# Peripherals.net
KiCad netlist of a schematic drawn in Altium Designer
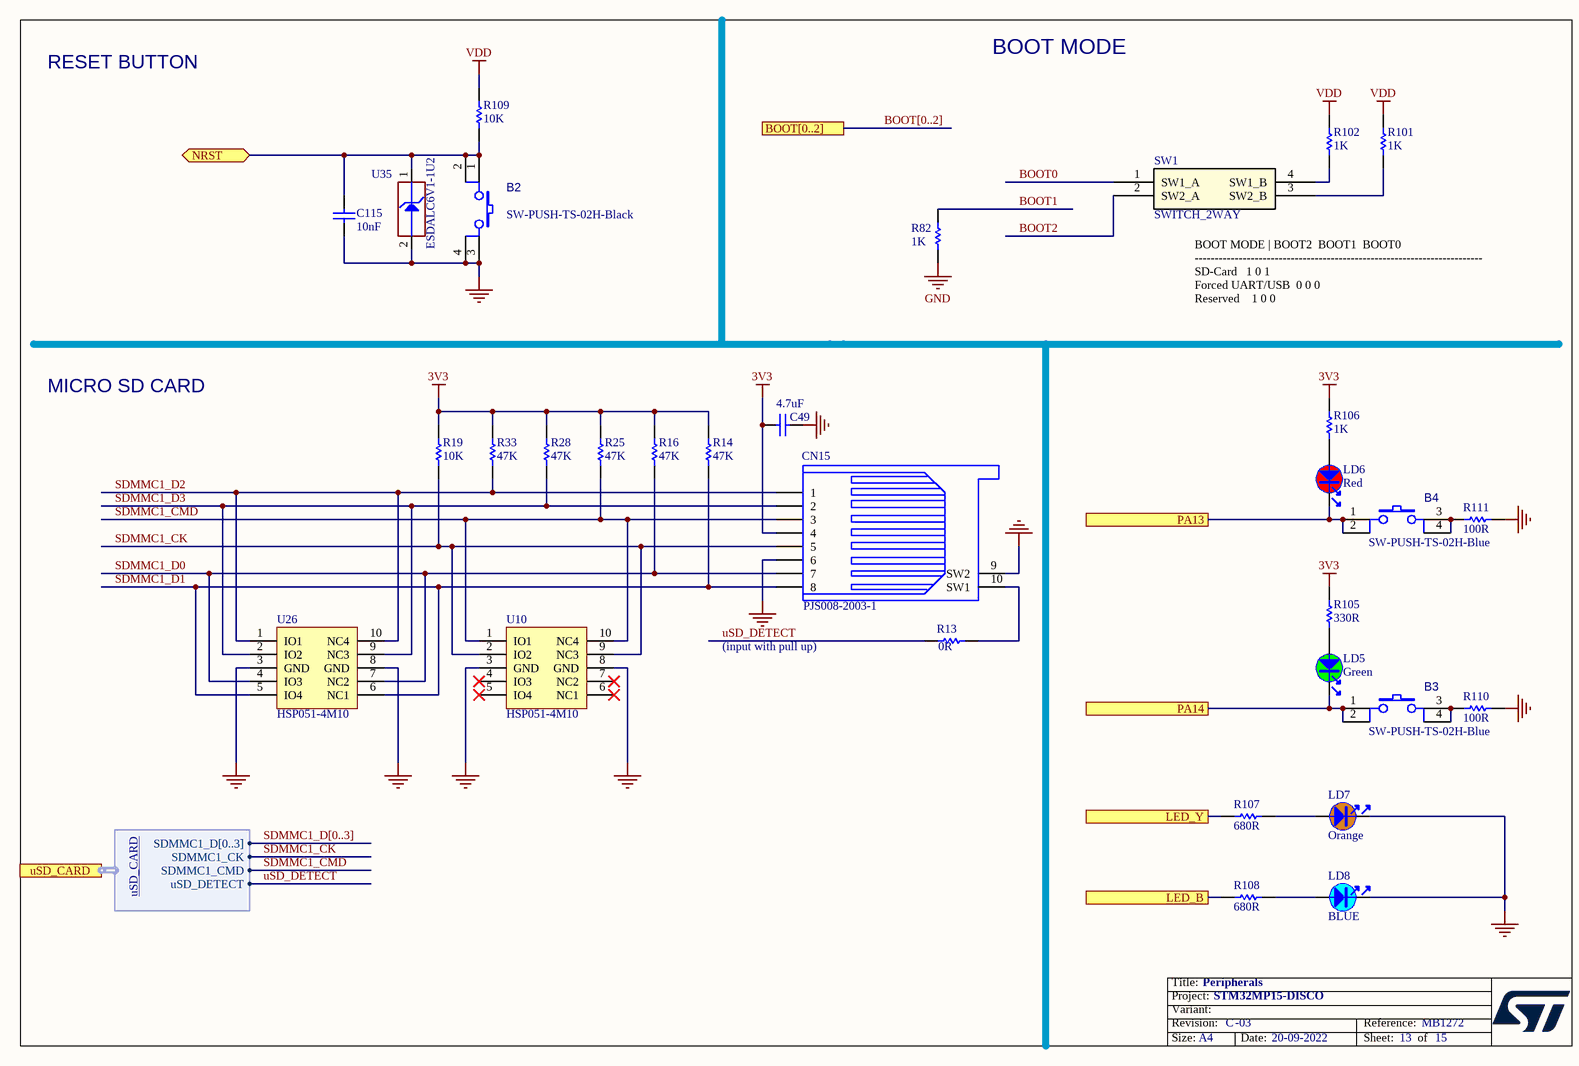
[diagram p0: Peripherals.SchDoc]

(export (version "E")
  (design (tool "Eeschema 10.0.6"))
  (components
    (comp (ref "B2")
      (value "SW-PUSH-TS-02H-Black")
      (footprint "SWI_JIUBABA_C-TS-02H-2-5-K-V-T_R_BLACK")
      (description "Switch HW SMD black")
      (fields
        (field (name "INTERNAL_PART_NUMBER") "MCD-00171")
        (field (name "MANUFACTURER_PART_NUMBER") "C-TS-02H-2.5-K-V-T/R BLACK")
        (field (name "PROVIDED_BY") "SUBCO")
      )
      (libsource (lib "MCD_PARTS_database") (part "SW-PUSH-TS-02H-Black"))
    )
    (comp (ref "B3")
      (value "SW-PUSH-TS-02H-Blue")
      (footprint "SWI_JIUBABA_C-TS-02H-2-5-B-V-T_R_BLUE")
      (description "Switch HW SMD blue")
      (fields
        (field (name "INTERNAL_PART_NUMBER") "MCD-00172")
        (field (name "MANUFACTURER_PART_NUMBER") "C-TS-02H-2.5-B-V-T/R BLUE")
        (field (name "PROVIDED_BY") "SUBCO")
      )
      (libsource (lib "MCD_PARTS_database") (part "SW-PUSH-TS-02H-Blue"))
    )
    (comp (ref "B4")
      (value "SW-PUSH-TS-02H-Blue")
      (footprint "SWI_JIUBABA_C-TS-02H-2-5-B-V-T_R_BLUE")
      (description "Switch HW SMD blue")
      (fields
        (field (name "INTERNAL_PART_NUMBER") "MCD-00172")
        (field (name "MANUFACTURER_PART_NUMBER") "C-TS-02H-2.5-B-V-T/R BLUE")
        (field (name "PROVIDED_BY") "SUBCO")
      )
      (libsource (lib "MCD_PARTS_database") (part "SW-PUSH-TS-02H-Blue"))
    )
    (comp (ref "C49")
      (value "4.7uF")
      (footprint "C0402")
      (description "Capacitor, MLCC, 4.7uF, 6V3, X5R, 20%, 0402, T=0,5mm")
      (fields
        (field (name "INTERNAL_PART_NUMBER") "MCD-01356")
        (field (name "MANUFACTURER_PART_NUMBER") "GRM155R60J475ME47")
        (field (name "PROVIDED_BY") "SUBCO")
      )
      (libsource (lib "MCD_PARTS_database") (part "Capacitor"))
    )
    (comp (ref "C115")
      (value "10nF")
      (footprint "C0402")
      (description "Capacitor, MLCC, 10nF, 16V, X7R, 10%, 0402, T=0.5mm")
      (fields
        (field (name "INTERNAL_PART_NUMBER") "MCD-00011")
        (field (name "MANUFACTURER_PART_NUMBER") "CC0402KRX7R7BB103")
        (field (name "PROVIDED_BY") "SUBCO")
      )
      (libsource (lib "MCD_PARTS_database") (part "Capacitor"))
    )
    (comp (ref "CN15")
      (value "PJS008-2003-1")
      (footprint "CON_MICROSD_YAMAICHI_PJS008-2003-0")
      (description "MicroSD Card Conn, Reversed-Type, Mnt Push-Push")
      (fields
        (field (name "INTERNAL_PART_NUMBER") "MCD-00023")
        (field (name "MANUFACTURER") "YAMAICHI")
        (field (name "PROVIDED_BY") "SUBCO")
      )
      (libsource (lib "MCD_PARTS_database") (part "microSD-PJS008-2003"))
    )
    (comp (ref "LD5")
      (value "Green")
      (footprint "LED_0603_GREEN")
      (description "LED, Green, 2V, 20mA, 0603")
      (fields (field (name "INTERNAL_PART_NUMBER") "MCD-02900") (field (name "MANUFACTURER") "EVERLIGHT"))
      (libsource (lib "MCD_PARTS_database") (part "LED_green"))
    )
    (comp (ref "LD6")
      (value "Red")
      (footprint "LED_0603_RED")
      (description "LED, Red, 2V35, 20mA, 0603")
      (fields (field (name "INTERNAL_PART_NUMBER") "MCD-02899") (field (name "MANUFACTURER") "EVERLIGHT"))
      (libsource (lib "MCD_PARTS_database") (part "LED_red"))
    )
    (comp (ref "LD7")
      (value "Orange")
      (footprint "LED_0603_ORANGE_H0P4")
      (description "LED, Orange, 2V2, 5mA, 0603")
      (fields (field (name "INTERNAL_PART_NUMBER") "MCD-02785") (field (name "MANUFACTURER") "EVERLIGHT"))
      (libsource (lib "MCD_PARTS_database") (part "LED_orange"))
    )
    (comp (ref "LD8")
      (value "BLUE")
      (footprint "LED_0603_SMD-B_BLUE_H0P4")
      (description "LED, Blue, VF: Min=2.5V, Max=3.1V, 10mA, 0603")
      (fields (field (name "INTERNAL_PART_NUMBER") "MCD-02786") (field (name "MANUFACTURER") "EVERLIGHT"))
      (libsource (lib "MCD_PARTS_database") (part "LED_blue"))
    )
    (comp (ref "R13")
      (value "0R")
      (footprint "R0402")
      (description "Resistor,0R,0402,5%,1/16W")
      (fields
        (field (name "INTERNAL_PART_NUMBER") "MCD-00052")
        (field (name "MANUFACTURER_PART_NUMBER") "RC0402JR-070RL")
        (field (name "PROVIDED_BY") "SUBCO")
      )
      (libsource (lib "MCD_PARTS_database") (part "Resistor"))
    )
    (comp (ref "R14")
      (value "47K")
      (footprint "R0402")
      (description "Resistor,47K,0402,1%,1/16W")
      (fields
        (field (name "INTERNAL_PART_NUMBER") "MCD-00063")
        (field (name "MANUFACTURER_PART_NUMBER") "RC0402FR-0747KL")
        (field (name "PROVIDED_BY") "SUBCO")
      )
      (libsource (lib "MCD_PARTS_database") (part "Resistor"))
    )
    (comp (ref "R16")
      (value "47K")
      (footprint "R0402")
      (description "Resistor,47K,0402,1%,1/16W")
      (fields
        (field (name "INTERNAL_PART_NUMBER") "MCD-00063")
        (field (name "MANUFACTURER_PART_NUMBER") "RC0402FR-0747KL")
        (field (name "PROVIDED_BY") "SUBCO")
      )
      (libsource (lib "MCD_PARTS_database") (part "Resistor"))
    )
    (comp (ref "R19")
      (value "10K")
      (footprint "R0402")
      (description "Resistor,10K,0402,1%,1/16W")
      (fields
        (field (name "INTERNAL_PART_NUMBER") "MCD-00053")
        (field (name "MANUFACTURER_PART_NUMBER") "RC0402FR-0710KL")
        (field (name "PROVIDED_BY") "SUBCO")
      )
      (libsource (lib "MCD_PARTS_database") (part "Resistor"))
    )
    (comp (ref "R25")
      (value "47K")
      (footprint "R0402")
      (description "Resistor,47K,0402,1%,1/16W")
      (fields
        (field (name "INTERNAL_PART_NUMBER") "MCD-00063")
        (field (name "MANUFACTURER_PART_NUMBER") "RC0402FR-0747KL")
        (field (name "PROVIDED_BY") "SUBCO")
      )
      (libsource (lib "MCD_PARTS_database") (part "Resistor"))
    )
    (comp (ref "R28")
      (value "47K")
      (footprint "R0402")
      (description "Resistor,47K,0402,1%,1/16W")
      (fields
        (field (name "INTERNAL_PART_NUMBER") "MCD-00063")
        (field (name "MANUFACTURER_PART_NUMBER") "RC0402FR-0747KL")
        (field (name "PROVIDED_BY") "SUBCO")
      )
      (libsource (lib "MCD_PARTS_database") (part "Resistor"))
    )
    (comp (ref "R33")
      (value "47K")
      (footprint "R0402")
      (description "Resistor,47K,0402,1%,1/16W")
      (fields
        (field (name "INTERNAL_PART_NUMBER") "MCD-00063")
        (field (name "MANUFACTURER_PART_NUMBER") "RC0402FR-0747KL")
        (field (name "PROVIDED_BY") "SUBCO")
      )
      (libsource (lib "MCD_PARTS_database") (part "Resistor"))
    )
    (comp (ref "R82")
      (value "1K")
      (footprint "R0402")
      (description "Resistor,1K,0402,1%,1/16W")
      (fields
        (field (name "INTERNAL_PART_NUMBER") "MCD-00061")
        (field (name "MANUFACTURER_PART_NUMBER") "RC0402FR-071KL")
        (field (name "PROVIDED_BY") "SUBCO")
      )
      (libsource (lib "MCD_PARTS_database") (part "Resistor"))
    )
    (comp (ref "R101")
      (value "1K")
      (footprint "R0402")
      (description "Resistor,1K,0402,1%,1/16W")
      (fields
        (field (name "INTERNAL_PART_NUMBER") "MCD-00061")
        (field (name "MANUFACTURER_PART_NUMBER") "RC0402FR-071KL")
        (field (name "PROVIDED_BY") "SUBCO")
      )
      (libsource (lib "MCD_PARTS_database") (part "Resistor"))
    )
    (comp (ref "R102")
      (value "1K")
      (footprint "R0402")
      (description "Resistor,1K,0402,1%,1/16W")
      (fields
        (field (name "INTERNAL_PART_NUMBER") "MCD-00061")
        (field (name "MANUFACTURER_PART_NUMBER") "RC0402FR-071KL")
        (field (name "PROVIDED_BY") "SUBCO")
      )
      (libsource (lib "MCD_PARTS_database") (part "Resistor"))
    )
    (comp (ref "R105")
      (value "330R")
      (footprint "R0402")
      (description "Resistor,330R,0402,1%,1/16W")
      (fields
        (field (name "INTERNAL_PART_NUMBER") "MCD-00062")
        (field (name "MANUFACTURER_PART_NUMBER") "RC0402FR-07330RL")
        (field (name "PROVIDED_BY") "SUBCO")
      )
      (libsource (lib "MCD_PARTS_database") (part "Resistor"))
    )
    (comp (ref "R106")
      (value "1K")
      (footprint "R0402")
      (description "Resistor,1K,0402,1%,1/16W")
      (fields
        (field (name "INTERNAL_PART_NUMBER") "MCD-00061")
        (field (name "MANUFACTURER_PART_NUMBER") "RC0402FR-071KL")
        (field (name "PROVIDED_BY") "SUBCO")
      )
      (libsource (lib "MCD_PARTS_database") (part "Resistor"))
    )
    (comp (ref "R107")
      (value "680R")
      (footprint "R0402")
      (description "Resistor,680R,0402,1%,1/16W")
      (fields
        (field (name "INTERNAL_PART_NUMBER") "MCD-00507")
        (field (name "MANUFACTURER_PART_NUMBER") "RC0402FR-07680RL")
        (field (name "PROVIDED_BY") "SUBCO")
      )
      (libsource (lib "MCD_PARTS_database") (part "Resistor"))
    )
    (comp (ref "R108")
      (value "680R")
      (footprint "R0402")
      (description "Resistor,680R,0402,1%,1/16W")
      (fields
        (field (name "INTERNAL_PART_NUMBER") "MCD-00507")
        (field (name "MANUFACTURER_PART_NUMBER") "RC0402FR-07680RL")
        (field (name "PROVIDED_BY") "SUBCO")
      )
      (libsource (lib "MCD_PARTS_database") (part "Resistor"))
    )
    (comp (ref "R109")
      (value "10K")
      (footprint "R0402")
      (description "Resistor,10K,0402,1%,1/16W")
      (fields
        (field (name "INTERNAL_PART_NUMBER") "MCD-00053")
        (field (name "MANUFACTURER_PART_NUMBER") "RC0402FR-0710KL")
        (field (name "PROVIDED_BY") "SUBCO")
      )
      (libsource (lib "MCD_PARTS_database") (part "Resistor"))
    )
    (comp (ref "R110")
      (value "100R")
      (footprint "R0402")
      (description "Resistor,100R,0402,1%,1/16W")
      (fields
        (field (name "INTERNAL_PART_NUMBER") "MCD-00067")
        (field (name "MANUFACTURER_PART_NUMBER") "RC0402FR-07100RL")
        (field (name "PROVIDED_BY") "SUBCO")
      )
      (libsource (lib "MCD_PARTS_database") (part "Resistor"))
    )
    (comp (ref "R111")
      (value "100R")
      (footprint "R0402")
      (description "Resistor,100R,0402,1%,1/16W")
      (fields
        (field (name "INTERNAL_PART_NUMBER") "MCD-00067")
        (field (name "MANUFACTURER_PART_NUMBER") "RC0402FR-07100RL")
        (field (name "PROVIDED_BY") "SUBCO")
      )
      (libsource (lib "MCD_PARTS_database") (part "Resistor"))
    )
    (comp (ref "SW1")
      (value "SWITCH_2WAY")
      (footprint "SWI_C&K_SDA02H1SBD_2POS")
      (description "Dip Switch ,2Position ,Surface Mount Slide (Standard) ,2.54 pitch,25mA 24VDC")
      (fields
        (field (name "INTERNAL_PART_NUMBER") "MCD-00658")
        (field (name "MANUFACTURER_PART_NUMBER") "SDA02H1SBD")
        (field (name "PROVIDED_BY") "SUBCO")
      )
      (libsource (lib "MCD_PARTS_database") (part "SWITCH_2WAY"))
    )
    (comp (ref "U10")
      (value "HSP051-4M10")
      (footprint "ESD_UQFN-10L_2P5X1_P050")
      (description "4-line ESD protection for high speed lines")
      (fields
        (field (name "INTERNAL_PART_NUMBER") "MCD-00667")
        (field (name "MANUFACTURER") "STMICROELECTRONICS")
        (field (name "PROVIDED_BY") "SUBCO with ST control")
      )
      (libsource (lib "MCD_PARTS_database") (part "HSP051-4M10"))
    )
    (comp (ref "U26")
      (value "HSP051-4M10")
      (footprint "ESD_UQFN-10L_2P5X1_P050")
      (description "4-line ESD protection for high speed lines")
      (fields
        (field (name "INTERNAL_PART_NUMBER") "MCD-00667")
        (field (name "MANUFACTURER") "STMICROELECTRONICS")
        (field (name "PROVIDED_BY") "SUBCO with ST control")
      )
      (libsource (lib "MCD_PARTS_database") (part "HSP051-4M10"))
    )
    (comp (ref "U35")
      (value "ESDALC6V1-1U2")
      (footprint "ESD_ST0201")
      (description "ESD protection 6V1")
      (fields
        (field (name "INTERNAL_PART_NUMBER") "MCD-00170")
        (field (name "MANUFACTURER") "STMICROELECTRONICS")
        (field (name "PROVIDED_BY") "SUBCO with ST control")
      )
      (libsource (lib "MCD_PARTS_database") (part "ESD-TRANSIL"))
    )
  )
  (nets
    (net (code "2") (name "/BOOT0") (class "Default")
      (node (ref "SW1") (pin "1") (pinfunction "SW1_A_1") (pintype "passive"))
    )
    (net (code "3") (name "/BOOT1") (class "Default")
      (node (ref "R82") (pin "2") (pinfunction "2_2") (pintype "passive"))
    )
    (net (code "4") (name "/BOOT2") (class "Default")
      (node (ref "SW1") (pin "2") (pinfunction "SW2_A_2") (pintype "passive"))
    )
    (net (code "6") (name "/LED_B") (class "Default")
      (node (ref "R108") (pin "1") (pinfunction "1_1") (pintype "passive"))
    )
    (net (code "7") (name "/LED_Y") (class "Default")
      (node (ref "R107") (pin "1") (pinfunction "1_1") (pintype "passive"))
    )
    (net (code "8") (name "/NRST") (class "Default")
      (node (ref "B2") (pin "1") (pinfunction "1_1") (pintype "passive"))
      (node (ref "B2") (pin "2") (pinfunction "2_2") (pintype "passive"))
      (node (ref "C115") (pin "2") (pinfunction "2_2") (pintype "passive"))
      (node (ref "R109") (pin "1") (pinfunction "1_1") (pintype "passive"))
      (node (ref "U35") (pin "1") (pinfunction "IO1_1") (pintype "passive"))
    )
    (net (code "9") (name "/PA13") (class "Default")
      (node (ref "B4") (pin "1") (pinfunction "1_1") (pintype "passive"))
      (node (ref "B4") (pin "2") (pinfunction "2_2") (pintype "passive"))
      (node (ref "LD6") (pin "2") (pintype "passive"))
    )
    (net (code "10") (name "/PA14") (class "Default")
      (node (ref "B3") (pin "1") (pinfunction "1_1") (pintype "passive"))
      (node (ref "B3") (pin "2") (pinfunction "2_2") (pintype "passive"))
      (node (ref "LD5") (pin "2") (pintype "passive"))
    )
    (net (code "11") (name "/SDMMC1_CK") (class "Default")
      (node (ref "CN15") (pin "5") (pinfunction "5_5") (pintype "passive"))
      (node (ref "R19") (pin "1") (pinfunction "1_1") (pintype "passive"))
      (node (ref "U10") (pin "2") (pinfunction "IO2_2") (pintype "passive"))
      (node (ref "U10") (pin "9") (pinfunction "NC3_9") (pintype "passive"))
    )
    (net (code "12") (name "/SDMMC1_CMD") (class "Default")
      (node (ref "CN15") (pin "3") (pinfunction "3_3") (pintype "passive"))
      (node (ref "R25") (pin "1") (pinfunction "1_1") (pintype "passive"))
      (node (ref "U10") (pin "1") (pinfunction "IO1_1") (pintype "passive"))
      (node (ref "U10") (pin "10") (pinfunction "NC4_10") (pintype "passive"))
    )
    (net (code "13") (name "/SDMMC1_D0") (class "Default")
      (node (ref "CN15") (pin "7") (pinfunction "7_7") (pintype "passive"))
      (node (ref "R16") (pin "1") (pinfunction "1_1") (pintype "passive"))
      (node (ref "U26") (pin "4") (pinfunction "IO3_4") (pintype "passive"))
      (node (ref "U26") (pin "7") (pinfunction "NC2_7") (pintype "passive"))
    )
    (net (code "14") (name "/SDMMC1_D1") (class "Default")
      (node (ref "CN15") (pin "8") (pinfunction "8_8") (pintype "passive"))
      (node (ref "R14") (pin "1") (pinfunction "1_1") (pintype "passive"))
      (node (ref "U26") (pin "5") (pinfunction "IO4_5") (pintype "passive"))
      (node (ref "U26") (pin "6") (pinfunction "NC1_6") (pintype "passive"))
    )
    (net (code "15") (name "/SDMMC1_D2") (class "Default")
      (node (ref "CN15") (pin "1") (pinfunction "1_1") (pintype "passive"))
      (node (ref "R33") (pin "1") (pinfunction "1_1") (pintype "passive"))
      (node (ref "U26") (pin "1") (pinfunction "IO1_1") (pintype "passive"))
      (node (ref "U26") (pin "10") (pinfunction "NC4_10") (pintype "passive"))
    )
    (net (code "16") (name "/SDMMC1_D3") (class "Default")
      (node (ref "CN15") (pin "2") (pinfunction "2_2") (pintype "passive"))
      (node (ref "R28") (pin "1") (pinfunction "1_1") (pintype "passive"))
      (node (ref "U26") (pin "2") (pinfunction "IO2_2") (pintype "passive"))
      (node (ref "U26") (pin "9") (pinfunction "NC3_9") (pintype "passive"))
    )
    (net (code "18") (name "/uSD_DETECT") (class "Default")
      (node (ref "R13") (pin "1") (pinfunction "1_1") (pintype "passive"))
    )
    (net (code "20") (name "3V3") (class "Default")
      (node (ref "C49") (pin "2") (pinfunction "2_2") (pintype "passive"))
      (node (ref "CN15") (pin "4") (pinfunction "4_4") (pintype "passive"))
      (node (ref "R105") (pin "2") (pinfunction "2_2") (pintype "passive"))
      (node (ref "R106") (pin "2") (pinfunction "2_2") (pintype "passive"))
      (node (ref "R14") (pin "2") (pinfunction "2_2") (pintype "passive"))
      (node (ref "R16") (pin "2") (pinfunction "2_2") (pintype "passive"))
      (node (ref "R19") (pin "2") (pinfunction "2_2") (pintype "passive"))
      (node (ref "R25") (pin "2") (pinfunction "2_2") (pintype "passive"))
      (node (ref "R28") (pin "2") (pinfunction "2_2") (pintype "passive"))
      (node (ref "R33") (pin "2") (pinfunction "2_2") (pintype "passive"))
    )
    (net (code "21") (name "GND") (class "Default")
      (node (ref "B2") (pin "3") (pinfunction "3_3") (pintype "passive"))
      (node (ref "B2") (pin "4") (pinfunction "4_4") (pintype "passive"))
      (node (ref "C115") (pin "1") (pinfunction "1_1") (pintype "passive"))
      (node (ref "C49") (pin "1") (pinfunction "1_1") (pintype "passive"))
      (node (ref "CN15") (pin "6") (pinfunction "6_6") (pintype "passive"))
      (node (ref "CN15") (pin "9") (pinfunction "SW2_9") (pintype "passive"))
      (node (ref "LD7") (pin "2") (pintype "passive"))
      (node (ref "LD8") (pin "2") (pintype "passive"))
      (node (ref "R110") (pin "2") (pinfunction "2_2") (pintype "passive"))
      (node (ref "R111") (pin "2") (pinfunction "2_2") (pintype "passive"))
      (node (ref "R82") (pin "1") (pinfunction "1_1") (pintype "passive"))
      (node (ref "U10") (pin "3") (pinfunction "GND_3") (pintype "passive"))
      (node (ref "U10") (pin "8") (pinfunction "GND_8") (pintype "passive"))
      (node (ref "U26") (pin "3") (pinfunction "GND_3") (pintype "passive"))
      (node (ref "U26") (pin "8") (pinfunction "GND_8") (pintype "passive"))
      (node (ref "U35") (pin "2") (pinfunction "GND_2") (pintype "passive"))
    )
    (net (code "22") (name "Net-(B3-Pad3)") (class "Default")
      (node (ref "B3") (pin "3") (pinfunction "3_3") (pintype "passive"))
      (node (ref "B3") (pin "4") (pinfunction "4_4") (pintype "passive"))
      (node (ref "R110") (pin "1") (pinfunction "1_1") (pintype "passive"))
    )
    (net (code "23") (name "Net-(B4-Pad3)") (class "Default")
      (node (ref "B4") (pin "3") (pinfunction "3_3") (pintype "passive"))
      (node (ref "B4") (pin "4") (pinfunction "4_4") (pintype "passive"))
      (node (ref "R111") (pin "1") (pinfunction "1_1") (pintype "passive"))
    )
    (net (code "24") (name "Net-(CN15-SW1)") (class "Default")
      (node (ref "CN15") (pin "10") (pinfunction "SW1_10") (pintype "passive"))
      (node (ref "R13") (pin "2") (pinfunction "2_2") (pintype "passive"))
    )
    (net (code "25") (name "Net-(LD5-Pad1)") (class "Default")
      (node (ref "LD5") (pin "1") (pintype "passive"))
      (node (ref "R105") (pin "1") (pinfunction "1_1") (pintype "passive"))
    )
    (net (code "26") (name "Net-(LD6-Pad1)") (class "Default")
      (node (ref "LD6") (pin "1") (pintype "passive"))
      (node (ref "R106") (pin "1") (pinfunction "1_1") (pintype "passive"))
    )
    (net (code "27") (name "Net-(LD7-Pad1)") (class "Default")
      (node (ref "LD7") (pin "1") (pintype "passive"))
      (node (ref "R107") (pin "2") (pinfunction "2_2") (pintype "passive"))
    )
    (net (code "28") (name "Net-(LD8-Pad1)") (class "Default")
      (node (ref "LD8") (pin "1") (pintype "passive"))
      (node (ref "R108") (pin "2") (pinfunction "2_2") (pintype "passive"))
    )
    (net (code "29") (name "Net-(SW1-SW1_B)") (class "Default")
      (node (ref "R102") (pin "1") (pinfunction "1_1") (pintype "passive"))
      (node (ref "SW1") (pin "4") (pinfunction "SW1_B_4") (pintype "passive"))
    )
    (net (code "30") (name "Net-(SW1-SW2_B)") (class "Default")
      (node (ref "R101") (pin "1") (pinfunction "1_1") (pintype "passive"))
      (node (ref "SW1") (pin "3") (pinfunction "SW2_B_3") (pintype "passive"))
    )
    (net (code "31") (name "VDD") (class "Default")
      (node (ref "R101") (pin "2") (pinfunction "2_2") (pintype "passive"))
      (node (ref "R102") (pin "2") (pinfunction "2_2") (pintype "passive"))
      (node (ref "R109") (pin "2") (pinfunction "2_2") (pintype "passive"))
    )
    (net (code "32") (name "unconnected-(U10-IO3-Pad4)") (class "Default")
      (node (ref "U10") (pin "4") (pinfunction "IO3_4") (pintype "passive+no_connect"))
    )
    (net (code "33") (name "unconnected-(U10-IO4-Pad5)") (class "Default")
      (node (ref "U10") (pin "5") (pinfunction "IO4_5") (pintype "passive+no_connect"))
    )
    (net (code "34") (name "unconnected-(U10-NC1-Pad6)") (class "Default")
      (node (ref "U10") (pin "6") (pinfunction "NC1_6") (pintype "passive+no_connect"))
    )
    (net (code "35") (name "unconnected-(U10-NC2-Pad7)") (class "Default")
      (node (ref "U10") (pin "7") (pinfunction "NC2_7") (pintype "passive+no_connect"))
    )
  )
)
